# easyeda.net
KiCad netlist of a schematic drawn in EasyEDA
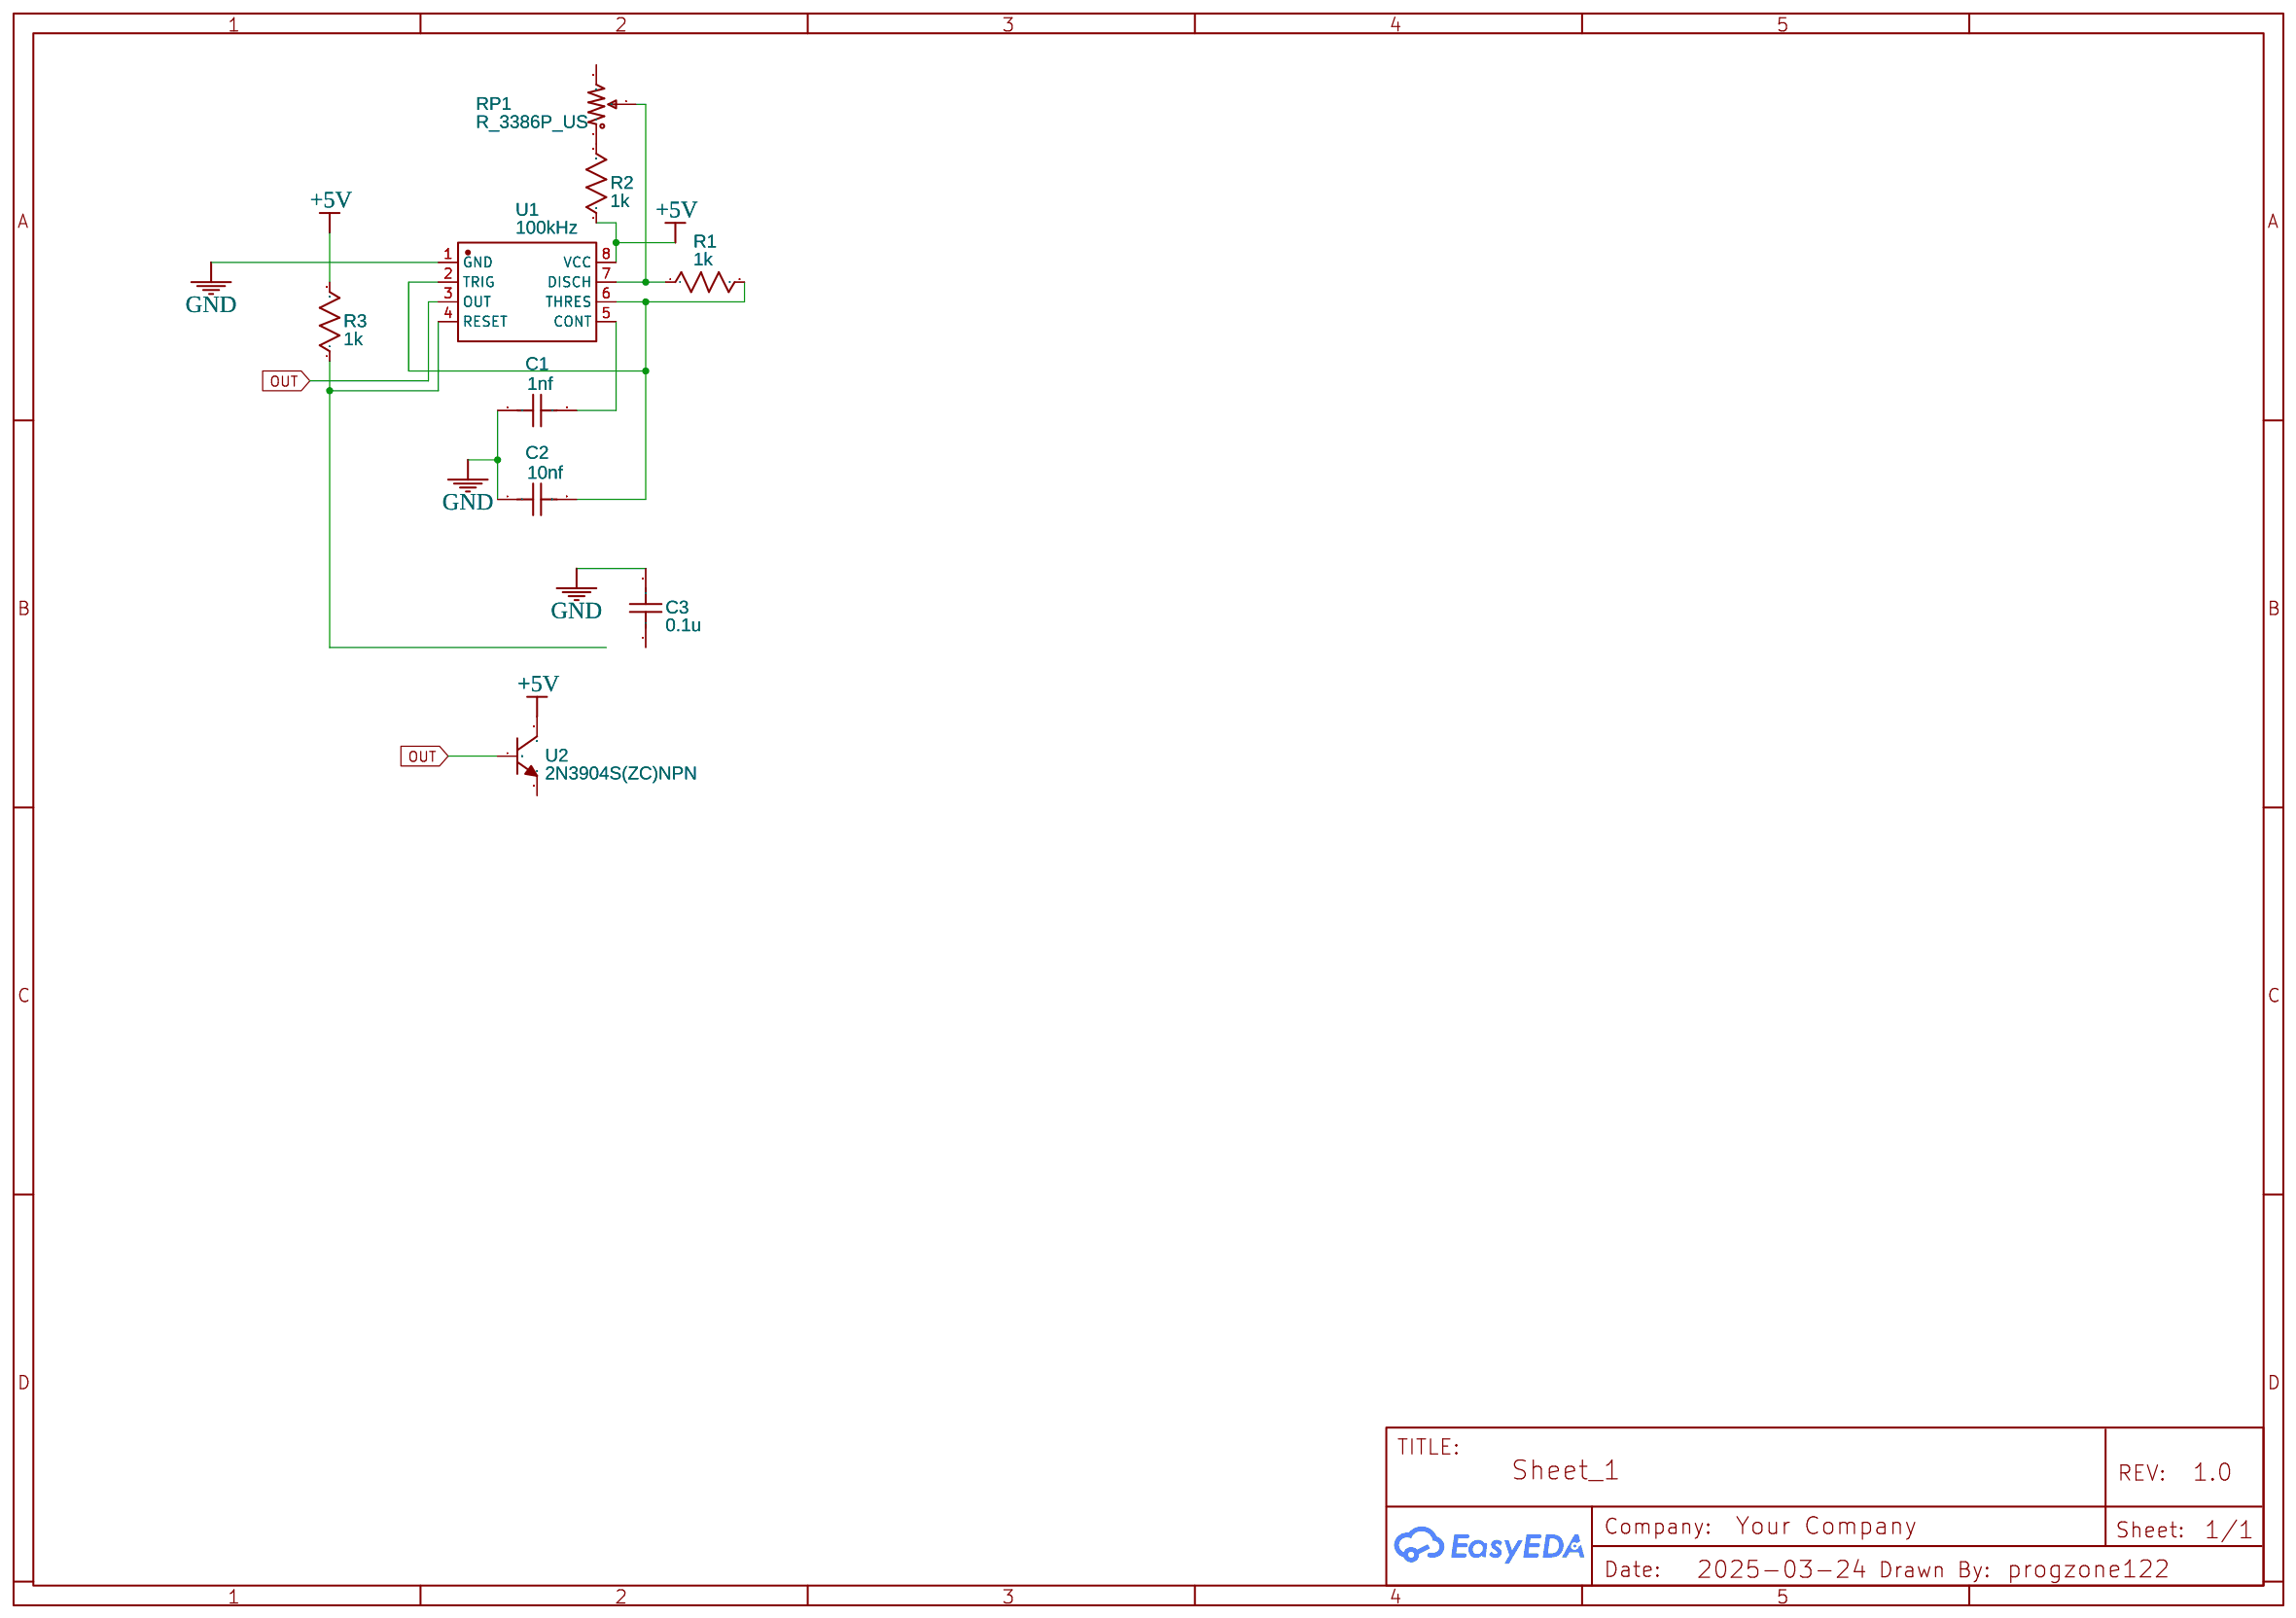
[diagram p0: schematic sheet]

(export (version "E")
  (design (tool "Eeschema 10.0.6"))
  (components
    (comp (ref "C1") (value "1nf") (libsource (lib "") (part "C_0603_US_1")))
    (comp (ref "C2") (value "10nf") (libsource (lib "") (part "C_0603_US_1")))
    (comp (ref "C3") (value "0.1u") (libsource (lib "") (part "C_0603_US")))
    (comp (ref "R1") (value "1k") (libsource (lib "") (part "R_0603_US")))
    (comp (ref "R2") (value "1k") (libsource (lib "") (part "R_0603_US_1")))
    (comp (ref "R3") (value "1k") (libsource (lib "") (part "R_0603_US_1")))
    (comp (ref "RP1") (value "R_3386P_US") (libsource (lib "") (part "R_3386P_US")))
    (comp (ref "U1")
      (value "100kHz")
      (fields (field (name "Manufacturer Part") "NE555P") (field (name "Manufacturer") "TI(德州仪器)"))
      (libsource (lib "") (part "NE555P"))
    )
    (comp (ref "U2") (value "2N3904S(ZC)NPN") (libsource (lib "") (part "2N3904S(ZC)NPN")))
  )
  (nets
    (net (code "1") (name "+5V") (class "Default")
      (node (ref "R2") (pin "1") (pinfunction "1_1") (pintype "unspecified"))
      (node (ref "R3") (pin "2") (pinfunction "2_2") (pintype "unspecified"))
      (node (ref "U1") (pin "8") (pinfunction "VCC_8") (pintype "unspecified"))
      (node (ref "U2") (pin "3") (pinfunction "C_3") (pintype "input"))
    )
    (net (code "2") (name "GND") (class "Default")
      (node (ref "C1") (pin "1") (pinfunction "1_1") (pintype "unspecified"))
      (node (ref "C2") (pin "1") (pinfunction "1_1") (pintype "unspecified"))
      (node (ref "C3") (pin "2") (pinfunction "2_2") (pintype "unspecified"))
      (node (ref "U1") (pin "1") (pinfunction "GND_1") (pintype "unspecified"))
    )
    (net (code "3") (name "Net-(R2-Pad2)") (class "Default")
      (node (ref "R2") (pin "2") (pinfunction "2_2") (pintype "unspecified"))
      (node (ref "RP1") (pin "1") (pinfunction "1_1") (pintype "unspecified"))
    )
    (net (code "4") (name "Net-(U1-CONT)") (class "Default")
      (node (ref "C1") (pin "2") (pinfunction "2_2") (pintype "unspecified"))
      (node (ref "U1") (pin "5") (pinfunction "CONT_5") (pintype "unspecified"))
    )
    (net (code "5") (name "Net-(U1-DISCH)") (class "Default")
      (node (ref "R1") (pin "1") (pinfunction "1_1") (pintype "unspecified"))
      (node (ref "RP1") (pin "2") (pinfunction "2_2") (pintype "unspecified"))
      (node (ref "U1") (pin "7") (pinfunction "DISCH_7") (pintype "unspecified"))
    )
    (net (code "6") (name "Net-(U1-RESET)") (class "Default")
      (node (ref "R3") (pin "1") (pinfunction "1_1") (pintype "unspecified"))
      (node (ref "U1") (pin "4") (pinfunction "RESET_4") (pintype "unspecified"))
    )
    (net (code "7") (name "Net-(U1-THRES)") (class "Default")
      (node (ref "C2") (pin "2") (pinfunction "2_2") (pintype "unspecified"))
      (node (ref "R1") (pin "2") (pinfunction "2_2") (pintype "unspecified"))
      (node (ref "U1") (pin "2") (pinfunction "TRIG_2") (pintype "unspecified"))
      (node (ref "U1") (pin "6") (pinfunction "THRES_6") (pintype "unspecified"))
    )
    (net (code "8") (name "OUT") (class "Default")
      (node (ref "U1") (pin "3") (pinfunction "OUT_3") (pintype "unspecified"))
      (node (ref "U2") (pin "1") (pinfunction "B_1") (pintype "input"))
    )
    (net (code "9") (name "unconnected-(C3-Pad1)") (class "Default")
      (node (ref "C3") (pin "1") (pinfunction "1_1") (pintype "unspecified"))
    )
    (net (code "10") (name "unconnected-(RP1-Pad3)") (class "Default")
      (node (ref "RP1") (pin "3") (pinfunction "3_3") (pintype "unspecified"))
    )
    (net (code "11") (name "unconnected-(U2-E-Pad2)") (class "Default")
      (node (ref "U2") (pin "2") (pinfunction "E_2") (pintype "input"))
    )
  )
)
